# HighAcc.net
KiCad netlist of a schematic drawn in EAGLE
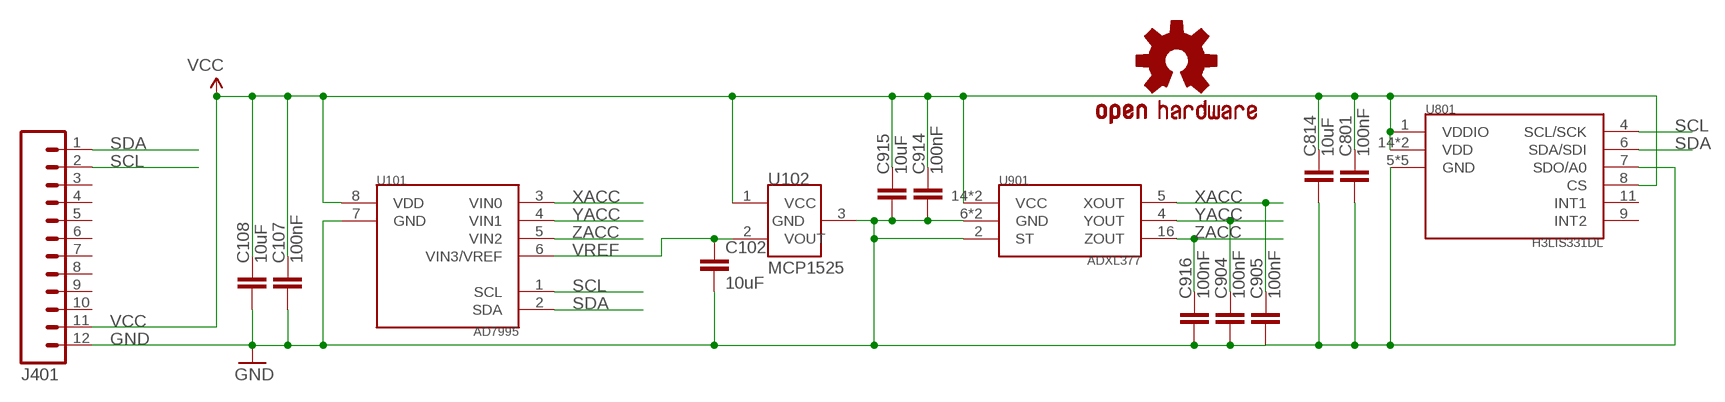
[diagram p0: schematic, sheet 1]

(export (version "E")
  (design (tool "Eeschema 10.0.6"))
  (components
    (comp (ref "C102")
      (value "10uF")
      (footprint "eagle-import:0603-CAP")
      (libsource (lib "eagle-import") (part "CAP0603-CAP"))
    )
    (comp (ref "C107")
      (value "100nF")
      (footprint "eagle-import:0603-CAP")
      (libsource (lib "eagle-import") (part "CAP0603-CAP"))
    )
    (comp (ref "C108")
      (value "10uF")
      (footprint "eagle-import:0603-CAP")
      (libsource (lib "eagle-import") (part "CAP0603-CAP"))
    )
    (comp (ref "C801")
      (value "100nF")
      (footprint "eagle-import:0603-CAP")
      (libsource (lib "eagle-import") (part "CAP0603-CAP"))
    )
    (comp (ref "C814")
      (value "10uF")
      (footprint "eagle-import:0603-CAP")
      (libsource (lib "eagle-import") (part "CAP0603-CAP"))
    )
    (comp (ref "C904")
      (value "100nF")
      (footprint "eagle-import:0603-CAP")
      (libsource (lib "eagle-import") (part "CAP0603-CAP"))
    )
    (comp (ref "C905")
      (value "100nF")
      (footprint "eagle-import:0603-CAP")
      (libsource (lib "eagle-import") (part "CAP0603-CAP"))
    )
    (comp (ref "C914")
      (value "100nF")
      (footprint "eagle-import:0603-CAP")
      (libsource (lib "eagle-import") (part "CAP0603-CAP"))
    )
    (comp (ref "C915")
      (value "10uF")
      (footprint "eagle-import:0603-CAP")
      (libsource (lib "eagle-import") (part "CAP0603-CAP"))
    )
    (comp (ref "C916")
      (value "100nF")
      (footprint "eagle-import:0603-CAP")
      (libsource (lib "eagle-import") (part "CAP0603-CAP"))
    )
    (comp (ref "J401")
      (value "M12PTH")
      (footprint "eagle-import:1X12")
      (libsource (lib "eagle-import") (part "M12PTH"))
    )
    (comp (ref "U$2")
      (value "OSHW-LOGOS")
      (footprint "eagle-import:OSHW-LOGO-S")
      (libsource (lib "eagle-import") (part "OSHW-LOGOS"))
    )
    (comp (ref "U101")
      (value "AD7995")
      (footprint "eagle-import:SOT-23-8")
      (libsource (lib "eagle-import") (part "AD799X"))
    )
    (comp (ref "U102")
      (value "MCP1525")
      (footprint "eagle-import:SOT-23-3")
      (libsource (lib "eagle-import") (part "MCP1525"))
    )
    (comp (ref "U801")
      (value "H3LIS331DL")
      (footprint "eagle-import:LLGA16")
      (libsource (lib "eagle-import") (part "H3LIS331DL"))
    )
    (comp (ref "U901")
      (value "ADXL377")
      (footprint "eagle-import:ADXL377")
      (libsource (lib "eagle-import") (part "ADXL377"))
    )
  )
  (nets
    (net (code "1") (name "/SCL") (class "Default")
      (node (ref "J401") (pin "2") (pinfunction "2_2") (pintype "passive"))
      (node (ref "U101") (pin "1") (pinfunction "SCL_1") (pintype "bidirectional"))
      (node (ref "U801") (pin "4") (pinfunction "SCL/SCK_4") (pintype "bidirectional"))
    )
    (net (code "2") (name "/SDA") (class "Default")
      (node (ref "J401") (pin "1") (pinfunction "1_1") (pintype "passive"))
      (node (ref "U101") (pin "2") (pinfunction "SDA_2") (pintype "bidirectional"))
      (node (ref "U801") (pin "6") (pinfunction "SDA/SDI_6") (pintype "bidirectional"))
    )
    (net (code "3") (name "/VREF") (class "Default")
      (node (ref "C102") (pin "1") (pinfunction "1_1") (pintype "passive"))
      (node (ref "U101") (pin "6") (pinfunction "VIN3/VREF_6") (pintype "bidirectional"))
      (node (ref "U102") (pin "2") (pinfunction "VOUT_2") (pintype "bidirectional"))
    )
    (net (code "4") (name "/XACC") (class "Default")
      (node (ref "C905") (pin "1") (pinfunction "1_1") (pintype "passive"))
      (node (ref "U101") (pin "3") (pinfunction "VIN0_3") (pintype "bidirectional"))
      (node (ref "U901") (pin "5") (pinfunction "XOUT_5") (pintype "bidirectional"))
    )
    (net (code "5") (name "/YACC") (class "Default")
      (node (ref "C904") (pin "1") (pinfunction "1_1") (pintype "passive"))
      (node (ref "U101") (pin "4") (pinfunction "VIN1_4") (pintype "bidirectional"))
      (node (ref "U901") (pin "4") (pinfunction "YOUT_4") (pintype "bidirectional"))
    )
    (net (code "6") (name "/ZACC") (class "Default")
      (node (ref "C916") (pin "1") (pinfunction "1_1") (pintype "passive"))
      (node (ref "U101") (pin "5") (pinfunction "VIN2_5") (pintype "bidirectional"))
      (node (ref "U901") (pin "16") (pinfunction "ZOUT_16") (pintype "bidirectional"))
    )
    (net (code "7") (name "GND") (class "Default")
      (node (ref "C102") (pin "2") (pinfunction "2_2") (pintype "passive"))
      (node (ref "C107") (pin "2") (pinfunction "2_2") (pintype "passive"))
      (node (ref "C108") (pin "2") (pinfunction "2_2") (pintype "passive"))
      (node (ref "C801") (pin "2") (pinfunction "2_2") (pintype "passive"))
      (node (ref "C814") (pin "2") (pinfunction "2_2") (pintype "passive"))
      (node (ref "C904") (pin "2") (pinfunction "2_2") (pintype "passive"))
      (node (ref "C905") (pin "2") (pinfunction "2_2") (pintype "passive"))
      (node (ref "C914") (pin "2") (pinfunction "2_2") (pintype "passive"))
      (node (ref "C915") (pin "2") (pinfunction "2_2") (pintype "passive"))
      (node (ref "C916") (pin "2") (pinfunction "2_2") (pintype "passive"))
      (node (ref "J401") (pin "12") (pinfunction "12_12") (pintype "passive"))
      (node (ref "U101") (pin "7") (pinfunction "GND_7") (pintype "bidirectional"))
      (node (ref "U102") (pin "3") (pinfunction "GND_3") (pintype "bidirectional"))
      (node (ref "U801") (pin "10") (pinfunction "GND_10") (pintype "bidirectional"))
      (node (ref "U801") (pin "12") (pinfunction "GND_12") (pintype "bidirectional"))
      (node (ref "U801") (pin "13") (pinfunction "GND_13") (pintype "bidirectional"))
      (node (ref "U801") (pin "16") (pinfunction "GND_16") (pintype "bidirectional"))
      (node (ref "U801") (pin "5") (pinfunction "GND_5") (pintype "bidirectional"))
      (node (ref "U801") (pin "7") (pinfunction "SDO/A0_7") (pintype "bidirectional"))
      (node (ref "U901") (pin "2") (pinfunction "ST_2") (pintype "bidirectional"))
      (node (ref "U901") (pin "6") (pinfunction "GND_6") (pintype "bidirectional"))
      (node (ref "U901") (pin "7") (pinfunction "GND_7") (pintype "bidirectional"))
    )
    (net (code "8") (name "VCC") (class "Default")
      (node (ref "C107") (pin "1") (pinfunction "1_1") (pintype "passive"))
      (node (ref "C108") (pin "1") (pinfunction "1_1") (pintype "passive"))
      (node (ref "C801") (pin "1") (pinfunction "1_1") (pintype "passive"))
      (node (ref "C814") (pin "1") (pinfunction "1_1") (pintype "passive"))
      (node (ref "C914") (pin "1") (pinfunction "1_1") (pintype "passive"))
      (node (ref "C915") (pin "1") (pinfunction "1_1") (pintype "passive"))
      (node (ref "J401") (pin "11") (pinfunction "11_11") (pintype "passive"))
      (node (ref "U101") (pin "8") (pinfunction "VDD_8") (pintype "bidirectional"))
      (node (ref "U102") (pin "1") (pinfunction "VCC_1") (pintype "bidirectional"))
      (node (ref "U801") (pin "1") (pinfunction "VDDIO_1") (pintype "bidirectional"))
      (node (ref "U801") (pin "14") (pinfunction "VDD_14") (pintype "bidirectional"))
      (node (ref "U801") (pin "15") (pinfunction "VDD_15") (pintype "bidirectional"))
      (node (ref "U801") (pin "8") (pinfunction "CS_8") (pintype "bidirectional"))
      (node (ref "U901") (pin "14") (pinfunction "VCC_14") (pintype "bidirectional"))
      (node (ref "U901") (pin "15") (pinfunction "VCC_15") (pintype "bidirectional"))
    )
    (net (code "9") (name "unconnected-(J401-Pad3)") (class "Default")
      (node (ref "J401") (pin "3") (pinfunction "3_3") (pintype "passive"))
    )
    (net (code "10") (name "unconnected-(J401-Pad4)") (class "Default")
      (node (ref "J401") (pin "4") (pinfunction "4_4") (pintype "passive"))
    )
    (net (code "11") (name "unconnected-(J401-Pad5)") (class "Default")
      (node (ref "J401") (pin "5") (pinfunction "5_5") (pintype "passive"))
    )
    (net (code "12") (name "unconnected-(J401-Pad6)") (class "Default")
      (node (ref "J401") (pin "6") (pinfunction "6_6") (pintype "passive"))
    )
    (net (code "13") (name "unconnected-(J401-Pad7)") (class "Default")
      (node (ref "J401") (pin "7") (pinfunction "7_7") (pintype "passive"))
    )
    (net (code "14") (name "unconnected-(J401-Pad8)") (class "Default")
      (node (ref "J401") (pin "8") (pinfunction "8_8") (pintype "passive"))
    )
    (net (code "15") (name "unconnected-(J401-Pad9)") (class "Default")
      (node (ref "J401") (pin "9") (pinfunction "9_9") (pintype "passive"))
    )
    (net (code "16") (name "unconnected-(J401-Pad10)") (class "Default")
      (node (ref "J401") (pin "10") (pinfunction "10_10") (pintype "passive"))
    )
    (net (code "17") (name "unconnected-(U801-INT1-Pad11)") (class "Default")
      (node (ref "U801") (pin "11") (pinfunction "INT1_11") (pintype "bidirectional"))
    )
    (net (code "18") (name "unconnected-(U801-INT2-Pad9)") (class "Default")
      (node (ref "U801") (pin "9") (pinfunction "INT2_9") (pintype "bidirectional"))
    )
  )
)
